# MAIN.net
KiCad netlist of a schematic drawn in Altium Designer
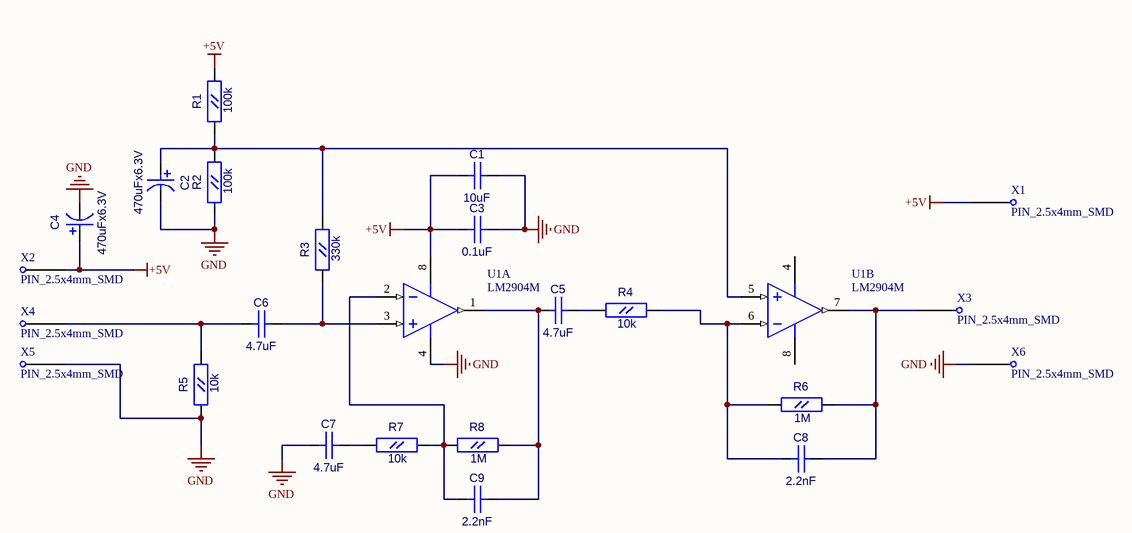
[diagram p0: MAIN.SchDoc]

(export (version "E")
  (design (tool "Eeschema 10.0.6"))
  (components
    (comp (ref "C1")
      (value "10uF")
      (footprint "CC0805")
      (description "CC0805")
      (libsource (lib "fizik_lib") (part "CC0805"))
    )
    (comp (ref "C2")
      (value "470uFx6.3V")
      (footprint "TAJ-D-1M")
      (description "TAJ-D")
      (libsource (lib "fizik_lib") (part "TAJ-D"))
    )
    (comp (ref "C3")
      (value "0.1uF")
      (footprint "CC0603")
      (description "CC0603")
      (libsource (lib "fizik_lib") (part "CC0603"))
    )
    (comp (ref "C4")
      (value "470uFx6.3V")
      (footprint "TAJ-D-1M")
      (description "TAJ-D")
      (libsource (lib "fizik_lib") (part "TAJ-D"))
    )
    (comp (ref "C5")
      (value "4.7uF")
      (footprint "CC0805")
      (description "CC0805")
      (libsource (lib "fizik_lib") (part "CC0805"))
    )
    (comp (ref "C6")
      (value "4.7uF")
      (footprint "CC0805")
      (description "CC0805")
      (libsource (lib "fizik_lib") (part "CC0805"))
    )
    (comp (ref "C7")
      (value "4.7uF")
      (footprint "CC0805")
      (description "CC0805")
      (libsource (lib "fizik_lib") (part "CC0805"))
    )
    (comp (ref "C8")
      (value "2.2nF")
      (footprint "CC0603")
      (description "CC0603")
      (libsource (lib "fizik_lib") (part "CC0603"))
    )
    (comp (ref "C9")
      (value "2.2nF")
      (footprint "CC0603")
      (description "CC0603")
      (libsource (lib "fizik_lib") (part "CC0603"))
    )
    (comp (ref "R1")
      (value "100k")
      (footprint "RC0603")
      (description "RC0603")
      (libsource (lib "fizik_lib") (part "RC0603"))
    )
    (comp (ref "R2")
      (value "100k")
      (footprint "RC0603")
      (description "RC0603")
      (libsource (lib "fizik_lib") (part "RC0603"))
    )
    (comp (ref "R3")
      (value "330k")
      (footprint "RC0603")
      (description "RC0603")
      (libsource (lib "fizik_lib") (part "RC0603"))
    )
    (comp (ref "R4")
      (value "10k")
      (footprint "RC0603")
      (description "RC0603")
      (libsource (lib "fizik_lib") (part "RC0603"))
    )
    (comp (ref "R5")
      (value "10k")
      (footprint "RC0603")
      (description "RC0603")
      (libsource (lib "fizik_lib") (part "RC0603"))
    )
    (comp (ref "R6")
      (value "1M")
      (footprint "RC0603")
      (description "RC0603")
      (libsource (lib "fizik_lib") (part "RC0603"))
    )
    (comp (ref "R7")
      (value "10k")
      (footprint "RC0603")
      (description "RC0603")
      (libsource (lib "fizik_lib") (part "RC0603"))
    )
    (comp (ref "R8")
      (value "1M")
      (footprint "RC0603")
      (description "RC0603")
      (libsource (lib "fizik_lib") (part "RC0603"))
    )
    (comp (ref "U1")
      (value "LM2904M")
      (footprint "M08A_N")
      (description "Low Power Dual Operational Amplifier, 8-pin Narrow SOIC")
      (fields
        (field (name "MANUFACTURER") "National Semiconductor")
        (field (name "PUBLISHER") "Altium Limited")
      )
      (libsource (lib "NSC Amplifier") (part "LM2904M"))
    )
    (comp (ref "X1")
      (value "PIN_2.5x4mm_SMD")
      (footprint "PIN_2.5x4mm_SMD")
      (libsource (lib "fizik_lib") (part "PIN_2.5x4mm_SMD"))
    )
    (comp (ref "X2")
      (value "PIN_2.5x4mm_SMD")
      (footprint "PIN_2.5x4mm_SMD")
      (libsource (lib "fizik_lib") (part "PIN_2.5x4mm_SMD"))
    )
    (comp (ref "X3")
      (value "PIN_2.5x4mm_SMD")
      (footprint "PIN_2.5x4mm_SMD")
      (libsource (lib "fizik_lib") (part "PIN_2.5x4mm_SMD"))
    )
    (comp (ref "X4")
      (value "PIN_2.5x4mm_SMD")
      (footprint "PIN_2.5x4mm_SMD")
      (libsource (lib "fizik_lib") (part "PIN_2.5x4mm_SMD"))
    )
    (comp (ref "X5")
      (value "PIN_2.5x4mm_SMD")
      (footprint "PIN_2.5x4mm_SMD")
      (libsource (lib "fizik_lib") (part "PIN_2.5x4mm_SMD"))
    )
    (comp (ref "X6")
      (value "PIN_2.5x4mm_SMD")
      (footprint "PIN_2.5x4mm_SMD")
      (libsource (lib "fizik_lib") (part "PIN_2.5x4mm_SMD"))
    )
  )
  (nets
    (net (code "1") (name "+5V") (class "Default")
      (node (ref "C1") (pin "1") (pinfunction "A_1") (pintype "passive"))
      (node (ref "C3") (pin "1") (pinfunction "A_1") (pintype "passive"))
      (node (ref "C4") (pin "1") (pinfunction "A_1") (pintype "passive"))
      (node (ref "R1") (pin "2") (pinfunction "B_2") (pintype "passive"))
      (node (ref "U1") (pin "8") (pinfunction "V+_8") (pintype "power_in"))
      (node (ref "X1") (pin "1") (pinfunction "1_1") (pintype "passive"))
      (node (ref "X2") (pin "1") (pinfunction "1_1") (pintype "passive"))
    )
    (net (code "2") (name "GND") (class "Default")
      (node (ref "C1") (pin "2") (pinfunction "B_2") (pintype "passive"))
      (node (ref "C2") (pin "2") (pinfunction "B_2") (pintype "passive"))
      (node (ref "C3") (pin "2") (pinfunction "B_2") (pintype "passive"))
      (node (ref "C4") (pin "2") (pinfunction "B_2") (pintype "passive"))
      (node (ref "C7") (pin "1") (pinfunction "A_1") (pintype "passive"))
      (node (ref "R2") (pin "1") (pinfunction "A_1") (pintype "passive"))
      (node (ref "R5") (pin "1") (pinfunction "A_1") (pintype "passive"))
      (node (ref "U1") (pin "4") (pinfunction "GND_4") (pintype "power_in"))
      (node (ref "X5") (pin "1") (pinfunction "1_1") (pintype "passive"))
      (node (ref "X6") (pin "1") (pinfunction "1_1") (pintype "passive"))
    )
    (net (code "3") (name "Net-(C2-A)") (class "Default")
      (node (ref "C2") (pin "1") (pinfunction "A_1") (pintype "passive"))
      (node (ref "R1") (pin "1") (pinfunction "A_1") (pintype "passive"))
      (node (ref "R2") (pin "2") (pinfunction "B_2") (pintype "passive"))
      (node (ref "R3") (pin "2") (pinfunction "B_2") (pintype "passive"))
      (node (ref "U1") (pin "5") (pinfunction "INB+_5") (pintype "input"))
    )
    (net (code "4") (name "Net-(C5-A)") (class "Default")
      (node (ref "C5") (pin "1") (pinfunction "A_1") (pintype "passive"))
      (node (ref "C9") (pin "2") (pinfunction "B_2") (pintype "passive"))
      (node (ref "R8") (pin "2") (pinfunction "B_2") (pintype "passive"))
      (node (ref "U1") (pin "1") (pinfunction "OUTA_1") (pintype "output"))
    )
    (net (code "5") (name "Net-(C5-B)") (class "Default")
      (node (ref "C5") (pin "2") (pinfunction "B_2") (pintype "passive"))
      (node (ref "R4") (pin "1") (pinfunction "A_1") (pintype "passive"))
    )
    (net (code "6") (name "Net-(C6-A)") (class "Default")
      (node (ref "C6") (pin "1") (pinfunction "A_1") (pintype "passive"))
      (node (ref "R5") (pin "2") (pinfunction "B_2") (pintype "passive"))
      (node (ref "X4") (pin "1") (pinfunction "1_1") (pintype "passive"))
    )
    (net (code "7") (name "Net-(C6-B)") (class "Default")
      (node (ref "C6") (pin "2") (pinfunction "B_2") (pintype "passive"))
      (node (ref "R3") (pin "1") (pinfunction "A_1") (pintype "passive"))
      (node (ref "U1") (pin "3") (pinfunction "INA+_3") (pintype "input"))
    )
    (net (code "8") (name "Net-(C7-B)") (class "Default")
      (node (ref "C7") (pin "2") (pinfunction "B_2") (pintype "passive"))
      (node (ref "R7") (pin "1") (pinfunction "A_1") (pintype "passive"))
    )
    (net (code "9") (name "Net-(C8-A)") (class "Default")
      (node (ref "C8") (pin "1") (pinfunction "A_1") (pintype "passive"))
      (node (ref "R4") (pin "2") (pinfunction "B_2") (pintype "passive"))
      (node (ref "R6") (pin "1") (pinfunction "A_1") (pintype "passive"))
      (node (ref "U1") (pin "6") (pinfunction "INB-_6") (pintype "input"))
    )
    (net (code "10") (name "Net-(C8-B)") (class "Default")
      (node (ref "C8") (pin "2") (pinfunction "B_2") (pintype "passive"))
      (node (ref "R6") (pin "2") (pinfunction "B_2") (pintype "passive"))
      (node (ref "U1") (pin "7") (pinfunction "OUTB_7") (pintype "output"))
      (node (ref "X3") (pin "1") (pinfunction "1_1") (pintype "passive"))
    )
    (net (code "11") (name "Net-(C9-A)") (class "Default")
      (node (ref "C9") (pin "1") (pinfunction "A_1") (pintype "passive"))
      (node (ref "R7") (pin "2") (pinfunction "B_2") (pintype "passive"))
      (node (ref "R8") (pin "1") (pinfunction "A_1") (pintype "passive"))
      (node (ref "U1") (pin "2") (pinfunction "INA-_2") (pintype "input"))
    )
    (net (code "12") (name "unconnected-(U1B-GND-Pad4)") (class "Default")
      (node (ref "U1") (pin "4") (pinfunction "GND_4") (pintype "power_in"))
    )
    (net (code "13") (name "unconnected-(U1B-V+-Pad8)") (class "Default")
      (node (ref "U1") (pin "8") (pinfunction "V+_8") (pintype "power_in"))
    )
  )
)
